# PowerSupply.net
KiCad netlist of a schematic drawn in Altium Designer
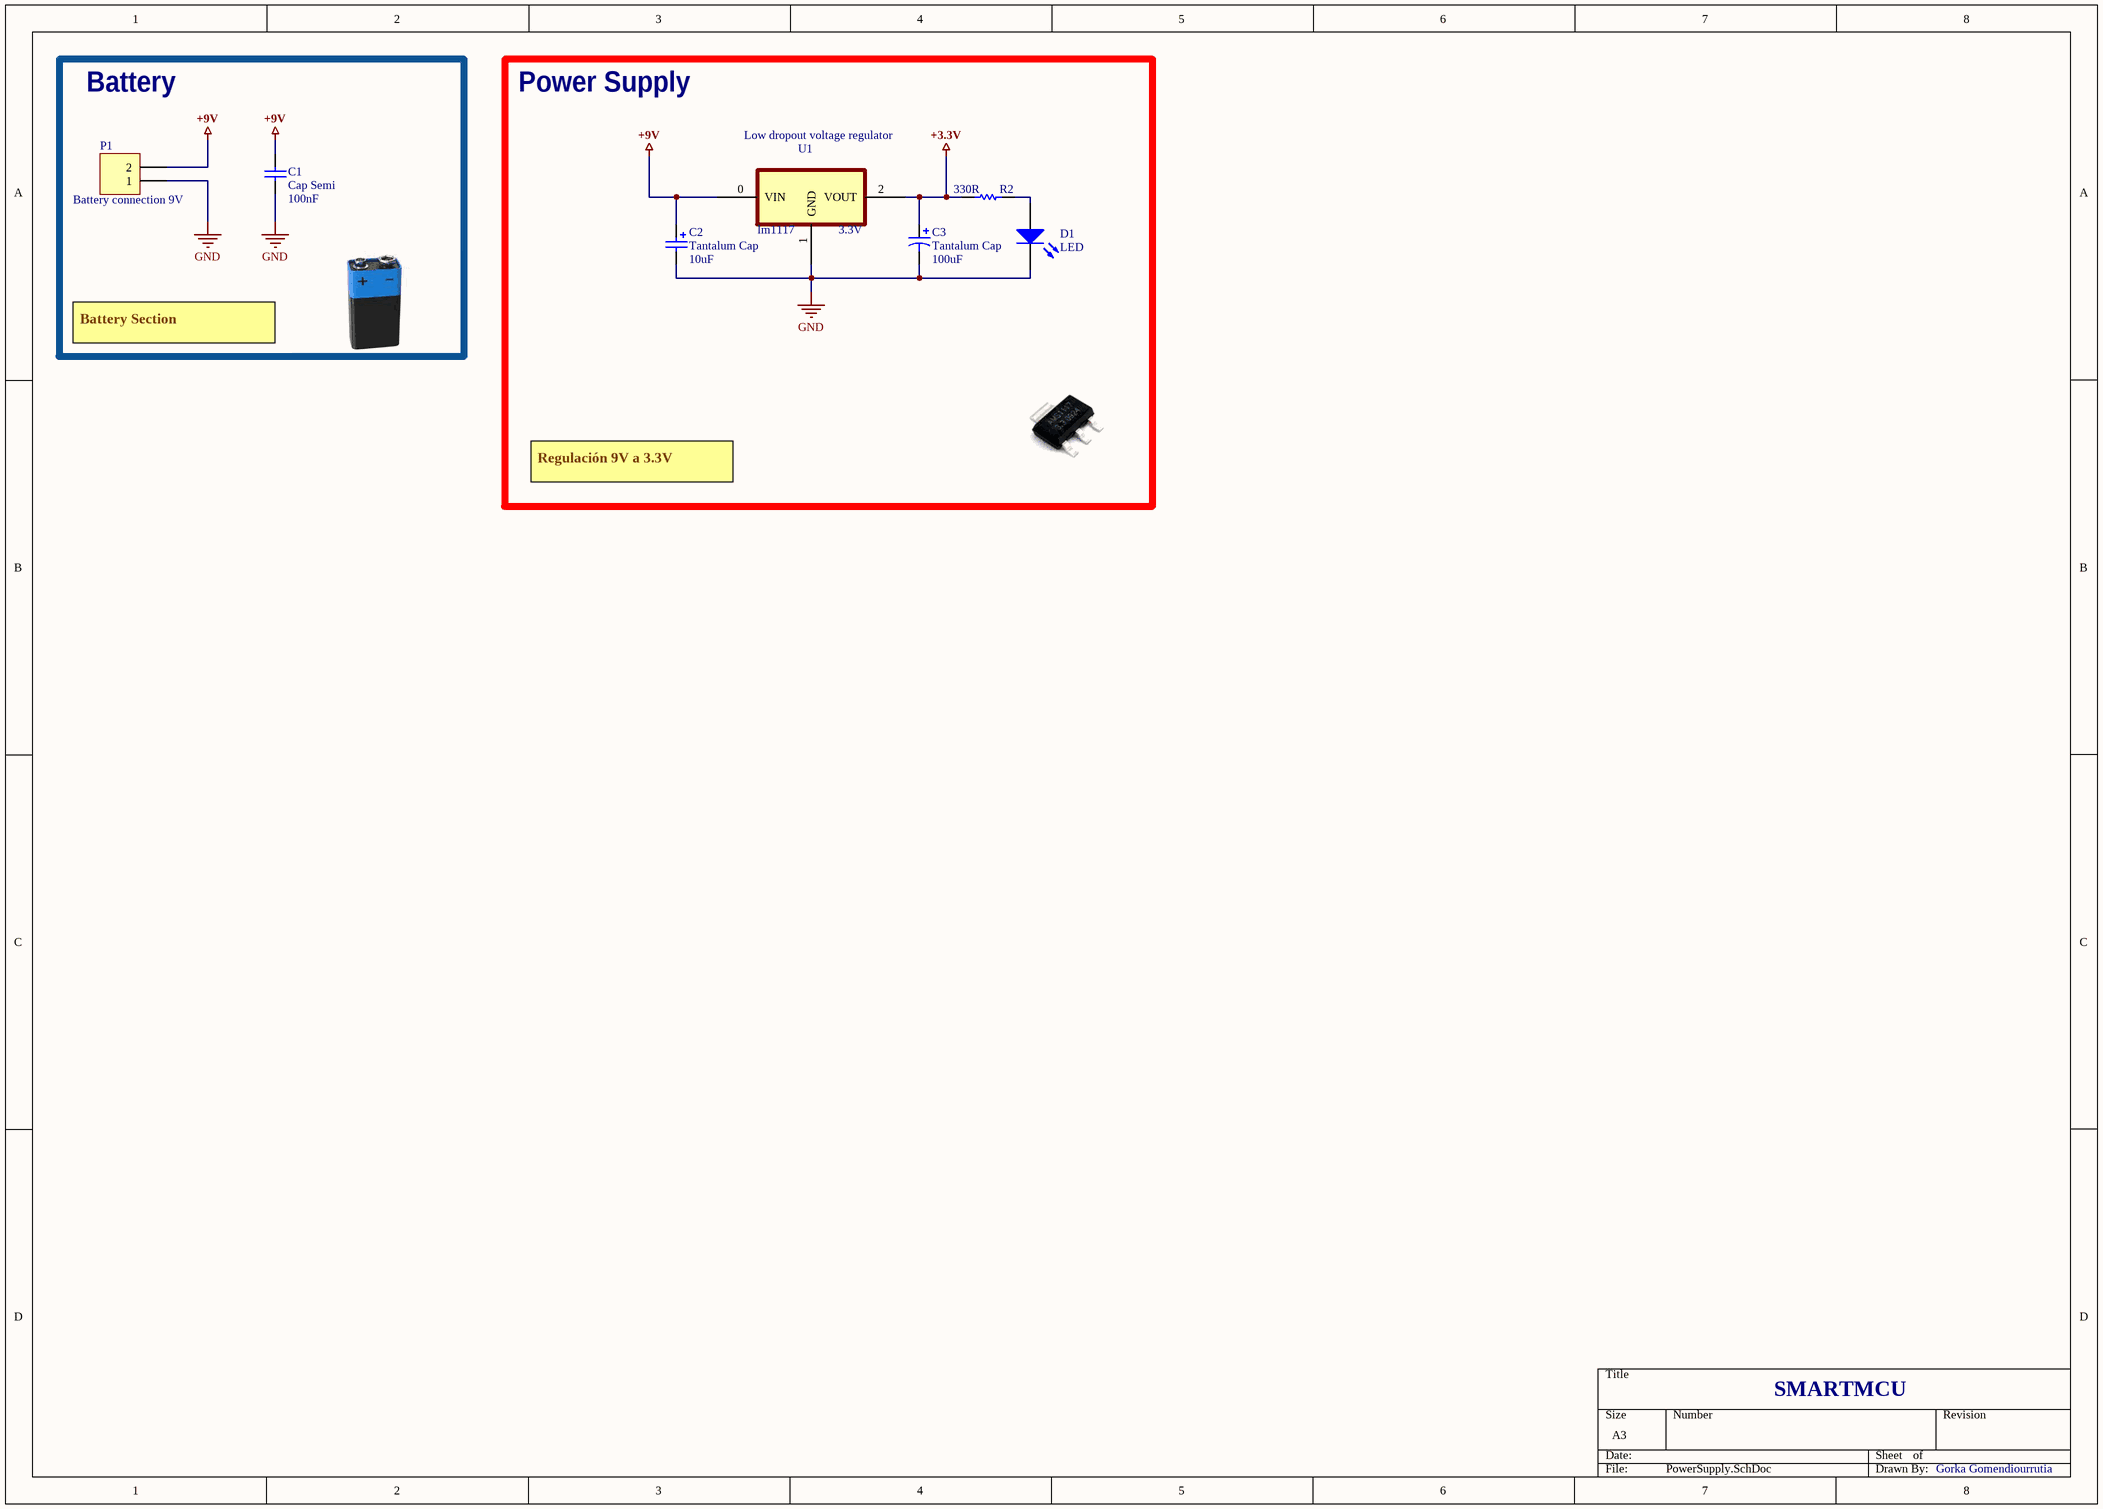
[diagram p0: PowerSupply.SchDoc]

(export (version "E")
  (design (tool "Eeschema 10.0.6"))
  (components
    (comp (ref "C1")
      (value "Cap Semi")
      (footprint "C1206")
      (description "Capacitor (Semiconductor SIM Model)  100nF")
      (fields (field (name "ALTIUM_VALUE") "100nF") (field (name "PUBLISHER") "Altium Limited"))
      (libsource (lib "Miscellaneous Devices") (part "Cap Semi"))
    )
    (comp (ref "C2")
      (value "Tantalum Cap")
      (footprint "C1206")
      (description "Polarized Capacitor (Radial)")
      (fields (field (name "ALTIUM_VALUE") "10uF") (field (name "PUBLISHER") "Altium Limited"))
      (libsource (lib "") (part "Cap Pol1_1"))
    )
    (comp (ref "C3")
      (value "Tantalum Cap")
      (footprint "C1206")
      (description "Polarized Capacitor (Radial)")
      (fields (field (name "ALTIUM_VALUE") "100uF") (field (name "PUBLISHER") "Altium Limited"))
      (libsource (lib "Miscellaneous Devices") (part "Cap Pol1"))
    )
    (comp (ref "D1")
      (value "LED")
      (footprint "MY_LED_0805")
      (description "Typical INFRARED GaAs LED")
      (fields (field (name "ASID PART NUMBER") "LED-AS"))
      (libsource (lib "Mylib+Rev+4") (part "LED"))
    )
    (comp (ref "P1")
      (value "Battery connection 9V")
      (footprint "HDR1X2H")
      (description "Header, 2-Pin, Right Angle")
      (fields (field (name "PUBLISHER") "Altium Limited"))
      (libsource (lib "Miscellaneous Connectors") (part "Header 2H"))
    )
    (comp (ref "R2")
      (value "330R")
      (footprint "MY_0805")
      (description "Standard resistor")
      (fields (field (name "ASID PART NUMBER") "Res-AS"))
      (libsource (lib "Mylib+Rev+4") (part "Res"))
    )
    (comp (ref "U1")
      (value "Low dropout voltage regulator")
      (footprint "4-Pin SOT")
      (fields (field (name "OUTPUT VOLTAGE") "3.3V") (field (name "MODELO") "lm1117"))
      (libsource (lib "MyLib") (part "lm1117"))
    )
  )
  (nets
    (net (code "1") (name "+3.3V") (class "Default")
      (node (ref "C3") (pin "2") (pinfunction "2_2") (pintype "passive"))
      (node (ref "R2") (pin "1") (pinfunction "1_1") (pintype "passive"))
      (node (ref "U1") (pin "2") (pinfunction "VOUT_2") (pintype "passive"))
    )
    (net (code "2") (name "+9V") (class "Default")
      (node (ref "C1") (pin "2") (pinfunction "2_2") (pintype "passive"))
      (node (ref "C2") (pin "2") (pinfunction "2_2") (pintype "passive"))
      (node (ref "P1") (pin "2") (pinfunction "2_2") (pintype "passive"))
      (node (ref "U1") (pin "0") (pinfunction "VIN_0") (pintype "passive"))
    )
    (net (code "3") (name "GND") (class "Default")
      (node (ref "C1") (pin "1") (pinfunction "1_1") (pintype "passive"))
      (node (ref "C2") (pin "1") (pinfunction "1_1") (pintype "passive"))
      (node (ref "C3") (pin "1") (pinfunction "1_1") (pintype "passive"))
      (node (ref "D1") (pin "K") (pinfunction "K_K") (pintype "passive"))
      (node (ref "P1") (pin "1") (pinfunction "1_1") (pintype "passive"))
      (node (ref "U1") (pin "1") (pinfunction "GND_1") (pintype "passive"))
    )
    (net (code "4") (name "Net-(D1-PadA)") (class "Default")
      (node (ref "D1") (pin "A") (pinfunction "A_A") (pintype "passive"))
      (node (ref "R2") (pin "2") (pinfunction "2_2") (pintype "passive"))
    )
  )
)
